# almo.net
KiCad netlist of a schematic drawn in EAGLE
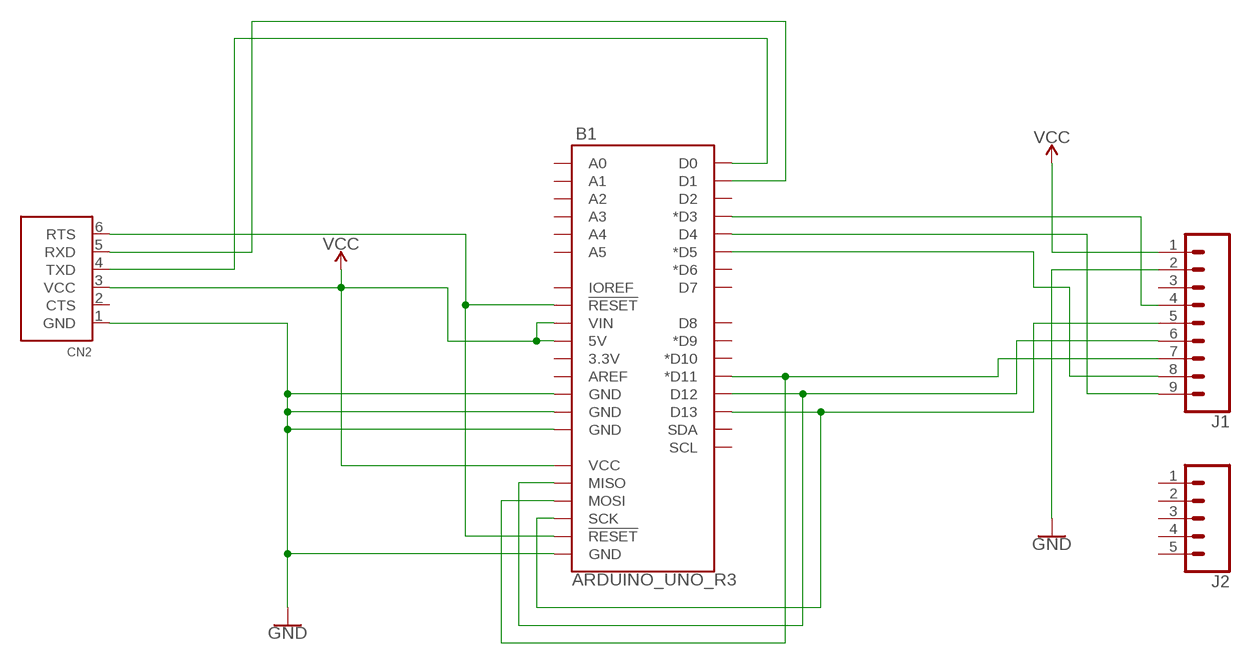
[diagram p0: schematic, sheet 1]

(export (version "E")
  (design (tool "Eeschema 10.0.6"))
  (components
    (comp (ref "B1")
      (value "ARDUINO_UNO_R3")
      (footprint "eagle-import:ARDUINO_R3")
      (libsource (lib "eagle-import") (part "ARDUINO_UNO_R3"))
    )
    (comp (ref "CN2")
      (value "FTDIUSBCABLE")
      (footprint "eagle-import:1X06_ROUND")
      (libsource (lib "eagle-import") (part "FTDIUSBCABLE"))
    )
    (comp (ref "J1")
      (value "CONN_09")
      (footprint "eagle-import:1X09")
      (libsource (lib "eagle-import") (part "CONN_09"))
    )
    (comp (ref "J2")
      (value "CONN_05")
      (footprint "eagle-import:1X05")
      (libsource (lib "eagle-import") (part "CONN_05"))
    )
  )
  (nets
    (net (code "1") (name "GND") (class "Default")
      (node (ref "B1") (pin "GND@1") (pinfunction "GND_GND@1") (pintype "bidirectional"))
      (node (ref "B1") (pin "GND@2") (pinfunction "GND_GND@2") (pintype "bidirectional"))
      (node (ref "B1") (pin "GND@3") (pinfunction "GND_GND@3") (pintype "bidirectional"))
      (node (ref "B1") (pin "GND@4") (pinfunction "GND_GND@4") (pintype "bidirectional"))
      (node (ref "CN2") (pin "1") (pinfunction "GND_1") (pintype "bidirectional"))
      (node (ref "J1") (pin "2") (pinfunction "2_2") (pintype "passive"))
    )
    (net (code "2") (name "Net-(B1-*D3)") (class "Default")
      (node (ref "B1") (pin "D3") (pinfunction "*D3_D3") (pintype "bidirectional"))
      (node (ref "J1") (pin "4") (pinfunction "4_4") (pintype "passive"))
    )
    (net (code "3") (name "Net-(B1-*D5)") (class "Default")
      (node (ref "B1") (pin "D5") (pinfunction "*D5_D5") (pintype "bidirectional"))
      (node (ref "J1") (pin "8") (pinfunction "8_8") (pintype "passive"))
    )
    (net (code "4") (name "Net-(B1-*D11)") (class "Default")
      (node (ref "B1") (pin "D11") (pinfunction "*D11_D11") (pintype "bidirectional"))
      (node (ref "B1") (pin "MOSI") (pinfunction "MOSI_MOSI") (pintype "bidirectional"))
      (node (ref "J1") (pin "7") (pinfunction "7_7") (pintype "passive"))
    )
    (net (code "5") (name "Net-(B1-PadD4)") (class "Default")
      (node (ref "B1") (pin "D4") (pinfunction "D4_D4") (pintype "bidirectional"))
      (node (ref "J1") (pin "9") (pinfunction "9_9") (pintype "passive"))
    )
    (net (code "6") (name "Net-(B1-PadD12)") (class "Default")
      (node (ref "B1") (pin "D12") (pinfunction "D12_D12") (pintype "bidirectional"))
      (node (ref "B1") (pin "MISO") (pinfunction "MISO_MISO") (pintype "bidirectional"))
      (node (ref "J1") (pin "6") (pinfunction "6_6") (pintype "passive"))
    )
    (net (code "7") (name "Net-(B1-PadD13)") (class "Default")
      (node (ref "B1") (pin "D13") (pinfunction "D13_D13") (pintype "bidirectional"))
      (node (ref "B1") (pin "SCK") (pinfunction "SCK_SCK") (pintype "bidirectional"))
      (node (ref "J1") (pin "5") (pinfunction "5_5") (pintype "passive"))
    )
    (net (code "8") (name "Net-(CN2-RTS)") (class "Default")
      (node (ref "B1") (pin "RESET@1") (pinfunction "~{RESET}_RESET@1") (pintype "bidirectional"))
      (node (ref "B1") (pin "RESET@2") (pinfunction "~{RESET}_RESET@2") (pintype "bidirectional"))
      (node (ref "CN2") (pin "6") (pinfunction "RTS_6") (pintype "bidirectional"))
    )
    (net (code "9") (name "Net-(CN2-RXD)") (class "Default")
      (node (ref "B1") (pin "D1") (pinfunction "D1_D1") (pintype "bidirectional"))
      (node (ref "CN2") (pin "5") (pinfunction "RXD_5") (pintype "bidirectional"))
    )
    (net (code "10") (name "Net-(CN2-TXD)") (class "Default")
      (node (ref "B1") (pin "D0") (pinfunction "D0_D0") (pintype "bidirectional"))
      (node (ref "CN2") (pin "4") (pinfunction "TXD_4") (pintype "bidirectional"))
    )
    (net (code "11") (name "VCC") (class "Default")
      (node (ref "B1") (pin "5V") (pinfunction "5V_5V") (pintype "bidirectional"))
      (node (ref "B1") (pin "VCC") (pinfunction "VCC_VCC") (pintype "bidirectional"))
      (node (ref "B1") (pin "VIN") (pinfunction "VIN_VIN") (pintype "bidirectional"))
      (node (ref "CN2") (pin "3") (pinfunction "VCC_3") (pintype "bidirectional"))
      (node (ref "J1") (pin "1") (pinfunction "1_1") (pintype "passive"))
    )
    (net (code "12") (name "unconnected-(B1-*D6-PadD6)") (class "Default")
      (node (ref "B1") (pin "D6") (pinfunction "*D6_D6") (pintype "bidirectional"))
    )
    (net (code "13") (name "unconnected-(B1-*D9-PadD9)") (class "Default")
      (node (ref "B1") (pin "D9") (pinfunction "*D9_D9") (pintype "bidirectional"))
    )
    (net (code "14") (name "unconnected-(B1-*D10-PadD10)") (class "Default")
      (node (ref "B1") (pin "D10") (pinfunction "*D10_D10") (pintype "bidirectional"))
    )
    (net (code "15") (name "unconnected-(B1-Pad3.3V)") (class "Default")
      (node (ref "B1") (pin "3.3V") (pinfunction "3.3V_3.3V") (pintype "bidirectional"))
    )
    (net (code "16") (name "unconnected-(B1-PadA0)") (class "Default")
      (node (ref "B1") (pin "A0") (pinfunction "A0_A0") (pintype "bidirectional"))
    )
    (net (code "17") (name "unconnected-(B1-PadA1)") (class "Default")
      (node (ref "B1") (pin "A1") (pinfunction "A1_A1") (pintype "bidirectional"))
    )
    (net (code "18") (name "unconnected-(B1-PadA2)") (class "Default")
      (node (ref "B1") (pin "A2") (pinfunction "A2_A2") (pintype "bidirectional"))
    )
    (net (code "19") (name "unconnected-(B1-PadA3)") (class "Default")
      (node (ref "B1") (pin "A3") (pinfunction "A3_A3") (pintype "bidirectional"))
    )
    (net (code "20") (name "unconnected-(B1-PadA4)") (class "Default")
      (node (ref "B1") (pin "A4") (pinfunction "A4_A4") (pintype "bidirectional"))
    )
    (net (code "21") (name "unconnected-(B1-PadA5)") (class "Default")
      (node (ref "B1") (pin "A5") (pinfunction "A5_A5") (pintype "bidirectional"))
    )
    (net (code "22") (name "unconnected-(B1-PadAREF)") (class "Default")
      (node (ref "B1") (pin "AREF") (pinfunction "AREF_AREF") (pintype "bidirectional"))
    )
    (net (code "23") (name "unconnected-(B1-PadD2)") (class "Default")
      (node (ref "B1") (pin "D2") (pinfunction "D2_D2") (pintype "bidirectional"))
    )
    (net (code "24") (name "unconnected-(B1-PadD7)") (class "Default")
      (node (ref "B1") (pin "D7") (pinfunction "D7_D7") (pintype "bidirectional"))
    )
    (net (code "25") (name "unconnected-(B1-PadD8)") (class "Default")
      (node (ref "B1") (pin "D8") (pinfunction "D8_D8") (pintype "bidirectional"))
    )
    (net (code "26") (name "unconnected-(B1-PadIOREF)") (class "Default")
      (node (ref "B1") (pin "IOREF") (pinfunction "IOREF_IOREF") (pintype "bidirectional"))
    )
    (net (code "27") (name "unconnected-(B1-PadSCL)") (class "Default")
      (node (ref "B1") (pin "SCL") (pinfunction "SCL_SCL") (pintype "bidirectional"))
    )
    (net (code "28") (name "unconnected-(B1-PadSDA)") (class "Default")
      (node (ref "B1") (pin "SDA") (pinfunction "SDA_SDA") (pintype "bidirectional"))
    )
    (net (code "29") (name "unconnected-(CN2-CTS-Pad2)") (class "Default")
      (node (ref "CN2") (pin "2") (pinfunction "CTS_2") (pintype "bidirectional"))
    )
    (net (code "30") (name "unconnected-(J1-Pad3)") (class "Default")
      (node (ref "J1") (pin "3") (pinfunction "3_3") (pintype "passive"))
    )
    (net (code "31") (name "unconnected-(J2-Pad1)") (class "Default")
      (node (ref "J2") (pin "1") (pinfunction "1_1") (pintype "passive"))
    )
    (net (code "32") (name "unconnected-(J2-Pad2)") (class "Default")
      (node (ref "J2") (pin "2") (pinfunction "2_2") (pintype "passive"))
    )
    (net (code "33") (name "unconnected-(J2-Pad3)") (class "Default")
      (node (ref "J2") (pin "3") (pinfunction "3_3") (pintype "passive"))
    )
    (net (code "34") (name "unconnected-(J2-Pad4)") (class "Default")
      (node (ref "J2") (pin "4") (pinfunction "4_4") (pintype "passive"))
    )
    (net (code "35") (name "unconnected-(J2-Pad5)") (class "Default")
      (node (ref "J2") (pin "5") (pinfunction "5_5") (pintype "passive"))
    )
  )
)
